# untitled3.net
KiCad netlist of a schematic drawn in EAGLE
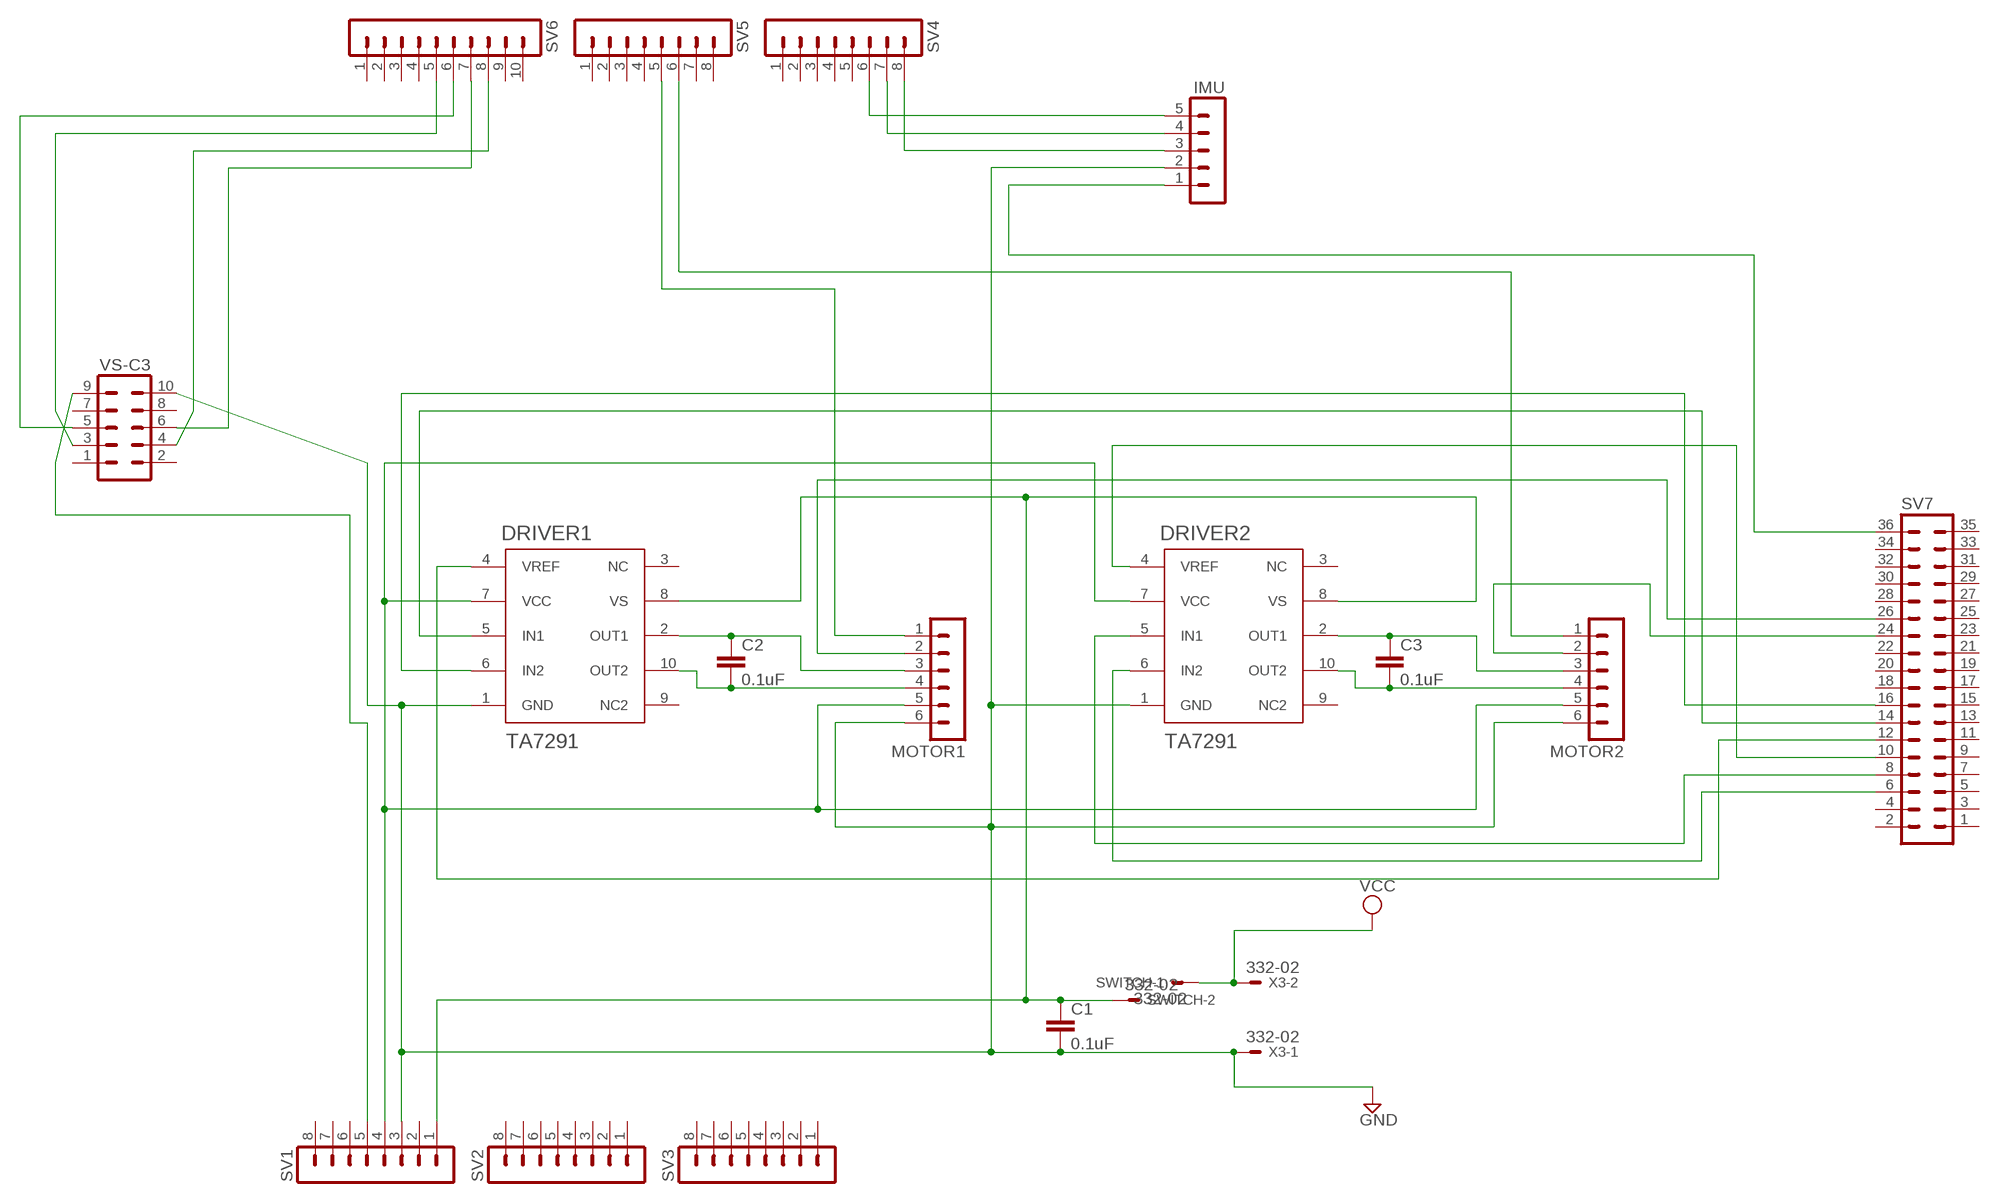
[diagram p0: schematic, sheet 1]

(export (version "E")
  (design (tool "Eeschema 10.0.6"))
  (components
    (comp (ref "C1")
      (value "0.1uF")
      (footprint "eagle-import:C5B2.5")
      (libsource (lib "eagle-import") (part "C5/2.5"))
    )
    (comp (ref "C2")
      (value "0.1uF")
      (footprint "eagle-import:C5B2.5")
      (libsource (lib "eagle-import") (part "C5/2.5"))
    )
    (comp (ref "C3")
      (value "0.1uF")
      (footprint "eagle-import:C5B2.5")
      (libsource (lib "eagle-import") (part "C5/2.5"))
    )
    (comp (ref "DRIVER1")
      (value "TA7291")
      (footprint "eagle-import:HSIP10")
      (libsource (lib "eagle-import") (part "TA7291"))
    )
    (comp (ref "DRIVER2")
      (value "TA7291")
      (footprint "eagle-import:HSIP10")
      (libsource (lib "eagle-import") (part "TA7291"))
    )
    (comp (ref "IMU")
      (value "MA05-1")
      (footprint "eagle-import:MA05-1")
      (libsource (lib "eagle-import") (part "MA05-1"))
    )
    (comp (ref "MOTOR1")
      (value "MA06-1")
      (footprint "eagle-import:MA06-1")
      (libsource (lib "eagle-import") (part "MA06-1"))
    )
    (comp (ref "MOTOR2")
      (value "MA06-1")
      (footprint "eagle-import:MA06-1")
      (libsource (lib "eagle-import") (part "MA06-1"))
    )
    (comp (ref "SV1")
      (value "MA08-1")
      (footprint "eagle-import:MA08-1")
      (libsource (lib "eagle-import") (part "MA08-1"))
    )
    (comp (ref "SV2")
      (value "MA08-1")
      (footprint "eagle-import:MA08-1")
      (libsource (lib "eagle-import") (part "MA08-1"))
    )
    (comp (ref "SV3")
      (value "MA08-1")
      (footprint "eagle-import:MA08-1")
      (libsource (lib "eagle-import") (part "MA08-1"))
    )
    (comp (ref "SV4")
      (value "MA08-1")
      (footprint "eagle-import:MA08-1")
      (libsource (lib "eagle-import") (part "MA08-1"))
    )
    (comp (ref "SV5")
      (value "MA08-1")
      (footprint "eagle-import:MA08-1")
      (libsource (lib "eagle-import") (part "MA08-1"))
    )
    (comp (ref "SV6")
      (value "MA10-1")
      (footprint "eagle-import:MA10-1")
      (libsource (lib "eagle-import") (part "MA10-1"))
    )
    (comp (ref "SV7")
      (value "MA18-2")
      (footprint "eagle-import:MA18-2")
      (libsource (lib "eagle-import") (part "MA18-2"))
    )
    (comp (ref "SWITCH")
      (value "332-02")
      (footprint "eagle-import:332-02")
      (libsource (lib "eagle-import") (part "332-02"))
    )
    (comp (ref "VS-C3")
      (value "MA05-2")
      (footprint "eagle-import:MA05-2")
      (libsource (lib "eagle-import") (part "MA05-2"))
    )
    (comp (ref "X3")
      (value "332-02")
      (footprint "eagle-import:332-02")
      (libsource (lib "eagle-import") (part "332-02"))
    )
  )
  (nets
    (net (code "1") (name "GND") (class "Default")
      (node (ref "C1") (pin "2") (pinfunction "2_2") (pintype "passive"))
      (node (ref "DRIVER1") (pin "1") (pinfunction "GND_1") (pintype "bidirectional"))
      (node (ref "DRIVER2") (pin "1") (pinfunction "GND_1") (pintype "bidirectional"))
      (node (ref "IMU") (pin "2") (pinfunction "2_2") (pintype "passive"))
      (node (ref "MOTOR1") (pin "6") (pinfunction "6_6") (pintype "passive"))
      (node (ref "MOTOR2") (pin "6") (pinfunction "6_6") (pintype "passive"))
      (node (ref "SV1") (pin "3") (pinfunction "3_3") (pintype "passive"))
      (node (ref "VS-C3") (pin "10") (pinfunction "10_10") (pintype "passive"))
      (node (ref "X3") (pin "1") (pinfunction "S_1") (pintype "passive"))
    )
    (net (code "2") (name "Net-(DRIVER1-IN1)") (class "Default")
      (node (ref "DRIVER1") (pin "5") (pinfunction "IN1_5") (pintype "bidirectional"))
      (node (ref "SV7") (pin "14") (pinfunction "14_14") (pintype "passive"))
    )
    (net (code "3") (name "Net-(DRIVER1-IN2)") (class "Default")
      (node (ref "DRIVER1") (pin "6") (pinfunction "IN2_6") (pintype "bidirectional"))
      (node (ref "SV7") (pin "16") (pinfunction "16_16") (pintype "passive"))
    )
    (net (code "4") (name "Net-(DRIVER1-OUT1)") (class "Default")
      (node (ref "C2") (pin "1") (pinfunction "1_1") (pintype "passive"))
      (node (ref "DRIVER1") (pin "2") (pinfunction "OUT1_2") (pintype "bidirectional"))
      (node (ref "MOTOR1") (pin "3") (pinfunction "3_3") (pintype "passive"))
    )
    (net (code "5") (name "Net-(DRIVER1-OUT2)") (class "Default")
      (node (ref "C2") (pin "2") (pinfunction "2_2") (pintype "passive"))
      (node (ref "DRIVER1") (pin "10") (pinfunction "OUT2_10") (pintype "bidirectional"))
      (node (ref "MOTOR1") (pin "4") (pinfunction "4_4") (pintype "passive"))
    )
    (net (code "6") (name "Net-(DRIVER1-VCC)") (class "Default")
      (node (ref "DRIVER1") (pin "7") (pinfunction "VCC_7") (pintype "bidirectional"))
      (node (ref "DRIVER2") (pin "7") (pinfunction "VCC_7") (pintype "bidirectional"))
      (node (ref "MOTOR1") (pin "5") (pinfunction "5_5") (pintype "passive"))
      (node (ref "MOTOR2") (pin "5") (pinfunction "5_5") (pintype "passive"))
      (node (ref "SV1") (pin "4") (pinfunction "4_4") (pintype "passive"))
    )
    (net (code "7") (name "Net-(DRIVER1-VREF)") (class "Default")
      (node (ref "DRIVER1") (pin "4") (pinfunction "VREF_4") (pintype "bidirectional"))
      (node (ref "SV7") (pin "12") (pinfunction "12_12") (pintype "passive"))
    )
    (net (code "8") (name "Net-(DRIVER1-VS)") (class "Default")
      (node (ref "C1") (pin "1") (pinfunction "1_1") (pintype "passive"))
      (node (ref "DRIVER1") (pin "8") (pinfunction "VS_8") (pintype "bidirectional"))
      (node (ref "DRIVER2") (pin "8") (pinfunction "VS_8") (pintype "bidirectional"))
      (node (ref "SV1") (pin "1") (pinfunction "1_1") (pintype "passive"))
      (node (ref "SWITCH") (pin "2") (pinfunction "S_2") (pintype "passive"))
    )
    (net (code "9") (name "Net-(DRIVER2-IN1)") (class "Default")
      (node (ref "DRIVER2") (pin "5") (pinfunction "IN1_5") (pintype "bidirectional"))
      (node (ref "SV7") (pin "8") (pinfunction "8_8") (pintype "passive"))
    )
    (net (code "10") (name "Net-(DRIVER2-IN2)") (class "Default")
      (node (ref "DRIVER2") (pin "6") (pinfunction "IN2_6") (pintype "bidirectional"))
      (node (ref "SV7") (pin "6") (pinfunction "6_6") (pintype "passive"))
    )
    (net (code "11") (name "Net-(DRIVER2-OUT1)") (class "Default")
      (node (ref "C3") (pin "1") (pinfunction "1_1") (pintype "passive"))
      (node (ref "DRIVER2") (pin "2") (pinfunction "OUT1_2") (pintype "bidirectional"))
      (node (ref "MOTOR2") (pin "3") (pinfunction "3_3") (pintype "passive"))
    )
    (net (code "12") (name "Net-(DRIVER2-OUT2)") (class "Default")
      (node (ref "C3") (pin "2") (pinfunction "2_2") (pintype "passive"))
      (node (ref "DRIVER2") (pin "10") (pinfunction "OUT2_10") (pintype "bidirectional"))
      (node (ref "MOTOR2") (pin "4") (pinfunction "4_4") (pintype "passive"))
    )
    (net (code "13") (name "Net-(DRIVER2-VREF)") (class "Default")
      (node (ref "DRIVER2") (pin "4") (pinfunction "VREF_4") (pintype "bidirectional"))
      (node (ref "SV7") (pin "10") (pinfunction "10_10") (pintype "passive"))
    )
    (net (code "14") (name "Net-(IMU-Pad1)") (class "Default")
      (node (ref "IMU") (pin "1") (pinfunction "1_1") (pintype "passive"))
      (node (ref "SV7") (pin "36") (pinfunction "36_36") (pintype "passive"))
    )
    (net (code "15") (name "Net-(IMU-Pad3)") (class "Default")
      (node (ref "IMU") (pin "3") (pinfunction "3_3") (pintype "passive"))
      (node (ref "SV4") (pin "8") (pinfunction "8_8") (pintype "passive"))
    )
    (net (code "16") (name "Net-(IMU-Pad4)") (class "Default")
      (node (ref "IMU") (pin "4") (pinfunction "4_4") (pintype "passive"))
      (node (ref "SV4") (pin "7") (pinfunction "7_7") (pintype "passive"))
    )
    (net (code "17") (name "Net-(IMU-Pad5)") (class "Default")
      (node (ref "IMU") (pin "5") (pinfunction "5_5") (pintype "passive"))
      (node (ref "SV4") (pin "6") (pinfunction "6_6") (pintype "passive"))
    )
    (net (code "18") (name "Net-(MOTOR1-Pad1)") (class "Default")
      (node (ref "MOTOR1") (pin "1") (pinfunction "1_1") (pintype "passive"))
      (node (ref "SV5") (pin "5") (pinfunction "5_5") (pintype "passive"))
    )
    (net (code "19") (name "Net-(MOTOR1-Pad2)") (class "Default")
      (node (ref "MOTOR1") (pin "2") (pinfunction "2_2") (pintype "passive"))
      (node (ref "SV7") (pin "26") (pinfunction "26_26") (pintype "passive"))
    )
    (net (code "20") (name "Net-(MOTOR2-Pad1)") (class "Default")
      (node (ref "MOTOR2") (pin "1") (pinfunction "1_1") (pintype "passive"))
      (node (ref "SV5") (pin "6") (pinfunction "6_6") (pintype "passive"))
    )
    (net (code "21") (name "Net-(MOTOR2-Pad2)") (class "Default")
      (node (ref "MOTOR2") (pin "2") (pinfunction "2_2") (pintype "passive"))
      (node (ref "SV7") (pin "24") (pinfunction "24_24") (pintype "passive"))
    )
    (net (code "22") (name "Net-(SV1-Pad5)") (class "Default")
      (node (ref "SV1") (pin "5") (pinfunction "5_5") (pintype "passive"))
      (node (ref "VS-C3") (pin "9") (pinfunction "9_9") (pintype "passive"))
    )
    (net (code "23") (name "Net-(SV6-Pad5)") (class "Default")
      (node (ref "SV6") (pin "5") (pinfunction "5_5") (pintype "passive"))
      (node (ref "VS-C3") (pin "3") (pinfunction "3_3") (pintype "passive"))
    )
    (net (code "24") (name "Net-(SV6-Pad6)") (class "Default")
      (node (ref "SV6") (pin "6") (pinfunction "6_6") (pintype "passive"))
      (node (ref "VS-C3") (pin "5") (pinfunction "5_5") (pintype "passive"))
    )
    (net (code "25") (name "Net-(SV6-Pad7)") (class "Default")
      (node (ref "SV6") (pin "7") (pinfunction "7_7") (pintype "passive"))
      (node (ref "VS-C3") (pin "6") (pinfunction "6_6") (pintype "passive"))
    )
    (net (code "26") (name "Net-(SV6-Pad8)") (class "Default")
      (node (ref "SV6") (pin "8") (pinfunction "8_8") (pintype "passive"))
      (node (ref "VS-C3") (pin "4") (pinfunction "4_4") (pintype "passive"))
    )
    (net (code "27") (name "VCC") (class "Default")
      (node (ref "SWITCH") (pin "1") (pinfunction "S_1") (pintype "passive"))
      (node (ref "X3") (pin "2") (pinfunction "S_2") (pintype "passive"))
    )
    (net (code "28") (name "unconnected-(DRIVER1-NC-Pad3)") (class "Default")
      (node (ref "DRIVER1") (pin "3") (pinfunction "NC_3") (pintype "bidirectional"))
    )
    (net (code "29") (name "unconnected-(DRIVER1-NC2-Pad9)") (class "Default")
      (node (ref "DRIVER1") (pin "9") (pinfunction "NC2_9") (pintype "bidirectional"))
    )
    (net (code "30") (name "unconnected-(DRIVER2-NC-Pad3)") (class "Default")
      (node (ref "DRIVER2") (pin "3") (pinfunction "NC_3") (pintype "bidirectional"))
    )
    (net (code "31") (name "unconnected-(DRIVER2-NC2-Pad9)") (class "Default")
      (node (ref "DRIVER2") (pin "9") (pinfunction "NC2_9") (pintype "bidirectional"))
    )
    (net (code "32") (name "unconnected-(SV1-Pad2)") (class "Default")
      (node (ref "SV1") (pin "2") (pinfunction "2_2") (pintype "passive"))
    )
    (net (code "33") (name "unconnected-(SV1-Pad6)") (class "Default")
      (node (ref "SV1") (pin "6") (pinfunction "6_6") (pintype "passive"))
    )
    (net (code "34") (name "unconnected-(SV1-Pad7)") (class "Default")
      (node (ref "SV1") (pin "7") (pinfunction "7_7") (pintype "passive"))
    )
    (net (code "35") (name "unconnected-(SV1-Pad8)") (class "Default")
      (node (ref "SV1") (pin "8") (pinfunction "8_8") (pintype "passive"))
    )
    (net (code "36") (name "unconnected-(SV2-Pad1)") (class "Default")
      (node (ref "SV2") (pin "1") (pinfunction "1_1") (pintype "passive"))
    )
    (net (code "37") (name "unconnected-(SV2-Pad2)") (class "Default")
      (node (ref "SV2") (pin "2") (pinfunction "2_2") (pintype "passive"))
    )
    (net (code "38") (name "unconnected-(SV2-Pad3)") (class "Default")
      (node (ref "SV2") (pin "3") (pinfunction "3_3") (pintype "passive"))
    )
    (net (code "39") (name "unconnected-(SV2-Pad4)") (class "Default")
      (node (ref "SV2") (pin "4") (pinfunction "4_4") (pintype "passive"))
    )
    (net (code "40") (name "unconnected-(SV2-Pad5)") (class "Default")
      (node (ref "SV2") (pin "5") (pinfunction "5_5") (pintype "passive"))
    )
    (net (code "41") (name "unconnected-(SV2-Pad6)") (class "Default")
      (node (ref "SV2") (pin "6") (pinfunction "6_6") (pintype "passive"))
    )
    (net (code "42") (name "unconnected-(SV2-Pad7)") (class "Default")
      (node (ref "SV2") (pin "7") (pinfunction "7_7") (pintype "passive"))
    )
    (net (code "43") (name "unconnected-(SV2-Pad8)") (class "Default")
      (node (ref "SV2") (pin "8") (pinfunction "8_8") (pintype "passive"))
    )
    (net (code "44") (name "unconnected-(SV3-Pad1)") (class "Default")
      (node (ref "SV3") (pin "1") (pinfunction "1_1") (pintype "passive"))
    )
    (net (code "45") (name "unconnected-(SV3-Pad2)") (class "Default")
      (node (ref "SV3") (pin "2") (pinfunction "2_2") (pintype "passive"))
    )
    (net (code "46") (name "unconnected-(SV3-Pad3)") (class "Default")
      (node (ref "SV3") (pin "3") (pinfunction "3_3") (pintype "passive"))
    )
    (net (code "47") (name "unconnected-(SV3-Pad4)") (class "Default")
      (node (ref "SV3") (pin "4") (pinfunction "4_4") (pintype "passive"))
    )
    (net (code "48") (name "unconnected-(SV3-Pad5)") (class "Default")
      (node (ref "SV3") (pin "5") (pinfunction "5_5") (pintype "passive"))
    )
    (net (code "49") (name "unconnected-(SV3-Pad6)") (class "Default")
      (node (ref "SV3") (pin "6") (pinfunction "6_6") (pintype "passive"))
    )
    (net (code "50") (name "unconnected-(SV3-Pad7)") (class "Default")
      (node (ref "SV3") (pin "7") (pinfunction "7_7") (pintype "passive"))
    )
    (net (code "51") (name "unconnected-(SV3-Pad8)") (class "Default")
      (node (ref "SV3") (pin "8") (pinfunction "8_8") (pintype "passive"))
    )
    (net (code "52") (name "unconnected-(SV4-Pad1)") (class "Default")
      (node (ref "SV4") (pin "1") (pinfunction "1_1") (pintype "passive"))
    )
    (net (code "53") (name "unconnected-(SV4-Pad2)") (class "Default")
      (node (ref "SV4") (pin "2") (pinfunction "2_2") (pintype "passive"))
    )
    (net (code "54") (name "unconnected-(SV4-Pad3)") (class "Default")
      (node (ref "SV4") (pin "3") (pinfunction "3_3") (pintype "passive"))
    )
    (net (code "55") (name "unconnected-(SV4-Pad4)") (class "Default")
      (node (ref "SV4") (pin "4") (pinfunction "4_4") (pintype "passive"))
    )
    (net (code "56") (name "unconnected-(SV4-Pad5)") (class "Default")
      (node (ref "SV4") (pin "5") (pinfunction "5_5") (pintype "passive"))
    )
    (net (code "57") (name "unconnected-(SV5-Pad1)") (class "Default")
      (node (ref "SV5") (pin "1") (pinfunction "1_1") (pintype "passive"))
    )
    (net (code "58") (name "unconnected-(SV5-Pad2)") (class "Default")
      (node (ref "SV5") (pin "2") (pinfunction "2_2") (pintype "passive"))
    )
    (net (code "59") (name "unconnected-(SV5-Pad3)") (class "Default")
      (node (ref "SV5") (pin "3") (pinfunction "3_3") (pintype "passive"))
    )
    (net (code "60") (name "unconnected-(SV5-Pad4)") (class "Default")
      (node (ref "SV5") (pin "4") (pinfunction "4_4") (pintype "passive"))
    )
    (net (code "61") (name "unconnected-(SV5-Pad7)") (class "Default")
      (node (ref "SV5") (pin "7") (pinfunction "7_7") (pintype "passive"))
    )
    (net (code "62") (name "unconnected-(SV5-Pad8)") (class "Default")
      (node (ref "SV5") (pin "8") (pinfunction "8_8") (pintype "passive"))
    )
    (net (code "63") (name "unconnected-(SV6-Pad1)") (class "Default")
      (node (ref "SV6") (pin "1") (pinfunction "1_1") (pintype "passive"))
    )
    (net (code "64") (name "unconnected-(SV6-Pad2)") (class "Default")
      (node (ref "SV6") (pin "2") (pinfunction "2_2") (pintype "passive"))
    )
    (net (code "65") (name "unconnected-(SV6-Pad3)") (class "Default")
      (node (ref "SV6") (pin "3") (pinfunction "3_3") (pintype "passive"))
    )
    (net (code "66") (name "unconnected-(SV6-Pad4)") (class "Default")
      (node (ref "SV6") (pin "4") (pinfunction "4_4") (pintype "passive"))
    )
    (net (code "67") (name "unconnected-(SV6-Pad9)") (class "Default")
      (node (ref "SV6") (pin "9") (pinfunction "9_9") (pintype "passive"))
    )
    (net (code "68") (name "unconnected-(SV6-Pad10)") (class "Default")
      (node (ref "SV6") (pin "10") (pinfunction "10_10") (pintype "passive"))
    )
    (net (code "69") (name "unconnected-(SV7-Pad1)") (class "Default")
      (node (ref "SV7") (pin "1") (pinfunction "1_1") (pintype "passive"))
    )
    (net (code "70") (name "unconnected-(SV7-Pad2)") (class "Default")
      (node (ref "SV7") (pin "2") (pinfunction "2_2") (pintype "passive"))
    )
    (net (code "71") (name "unconnected-(SV7-Pad3)") (class "Default")
      (node (ref "SV7") (pin "3") (pinfunction "3_3") (pintype "passive"))
    )
    (net (code "72") (name "unconnected-(SV7-Pad4)") (class "Default")
      (node (ref "SV7") (pin "4") (pinfunction "4_4") (pintype "passive"))
    )
    (net (code "73") (name "unconnected-(SV7-Pad5)") (class "Default")
      (node (ref "SV7") (pin "5") (pinfunction "5_5") (pintype "passive"))
    )
    (net (code "74") (name "unconnected-(SV7-Pad7)") (class "Default")
      (node (ref "SV7") (pin "7") (pinfunction "7_7") (pintype "passive"))
    )
    (net (code "75") (name "unconnected-(SV7-Pad9)") (class "Default")
      (node (ref "SV7") (pin "9") (pinfunction "9_9") (pintype "passive"))
    )
    (net (code "76") (name "unconnected-(SV7-Pad11)") (class "Default")
      (node (ref "SV7") (pin "11") (pinfunction "11_11") (pintype "passive"))
    )
    (net (code "77") (name "unconnected-(SV7-Pad13)") (class "Default")
      (node (ref "SV7") (pin "13") (pinfunction "13_13") (pintype "passive"))
    )
    (net (code "78") (name "unconnected-(SV7-Pad15)") (class "Default")
      (node (ref "SV7") (pin "15") (pinfunction "15_15") (pintype "passive"))
    )
    (net (code "79") (name "unconnected-(SV7-Pad17)") (class "Default")
      (node (ref "SV7") (pin "17") (pinfunction "17_17") (pintype "passive"))
    )
    (net (code "80") (name "unconnected-(SV7-Pad18)") (class "Default")
      (node (ref "SV7") (pin "18") (pinfunction "18_18") (pintype "passive"))
    )
    (net (code "81") (name "unconnected-(SV7-Pad19)") (class "Default")
      (node (ref "SV7") (pin "19") (pinfunction "19_19") (pintype "passive"))
    )
    (net (code "82") (name "unconnected-(SV7-Pad20)") (class "Default")
      (node (ref "SV7") (pin "20") (pinfunction "20_20") (pintype "passive"))
    )
    (net (code "83") (name "unconnected-(SV7-Pad21)") (class "Default")
      (node (ref "SV7") (pin "21") (pinfunction "21_21") (pintype "passive"))
    )
    (net (code "84") (name "unconnected-(SV7-Pad22)") (class "Default")
      (node (ref "SV7") (pin "22") (pinfunction "22_22") (pintype "passive"))
    )
    (net (code "85") (name "unconnected-(SV7-Pad23)") (class "Default")
      (node (ref "SV7") (pin "23") (pinfunction "23_23") (pintype "passive"))
    )
    (net (code "86") (name "unconnected-(SV7-Pad25)") (class "Default")
      (node (ref "SV7") (pin "25") (pinfunction "25_25") (pintype "passive"))
    )
    (net (code "87") (name "unconnected-(SV7-Pad27)") (class "Default")
      (node (ref "SV7") (pin "27") (pinfunction "27_27") (pintype "passive"))
    )
    (net (code "88") (name "unconnected-(SV7-Pad28)") (class "Default")
      (node (ref "SV7") (pin "28") (pinfunction "28_28") (pintype "passive"))
    )
    (net (code "89") (name "unconnected-(SV7-Pad29)") (class "Default")
      (node (ref "SV7") (pin "29") (pinfunction "29_29") (pintype "passive"))
    )
    (net (code "90") (name "unconnected-(SV7-Pad30)") (class "Default")
      (node (ref "SV7") (pin "30") (pinfunction "30_30") (pintype "passive"))
    )
    (net (code "91") (name "unconnected-(SV7-Pad31)") (class "Default")
      (node (ref "SV7") (pin "31") (pinfunction "31_31") (pintype "passive"))
    )
    (net (code "92") (name "unconnected-(SV7-Pad32)") (class "Default")
      (node (ref "SV7") (pin "32") (pinfunction "32_32") (pintype "passive"))
    )
    (net (code "93") (name "unconnected-(SV7-Pad33)") (class "Default")
      (node (ref "SV7") (pin "33") (pinfunction "33_33") (pintype "passive"))
    )
    (net (code "94") (name "unconnected-(SV7-Pad34)") (class "Default")
      (node (ref "SV7") (pin "34") (pinfunction "34_34") (pintype "passive"))
    )
    (net (code "95") (name "unconnected-(SV7-Pad35)") (class "Default")
      (node (ref "SV7") (pin "35") (pinfunction "35_35") (pintype "passive"))
    )
    (net (code "96") (name "unconnected-(VS-C3-Pad1)") (class "Default")
      (node (ref "VS-C3") (pin "1") (pinfunction "1_1") (pintype "passive"))
    )
    (net (code "97") (name "unconnected-(VS-C3-Pad2)") (class "Default")
      (node (ref "VS-C3") (pin "2") (pinfunction "2_2") (pintype "passive"))
    )
    (net (code "98") (name "unconnected-(VS-C3-Pad7)") (class "Default")
      (node (ref "VS-C3") (pin "7") (pinfunction "7_7") (pintype "passive"))
    )
    (net (code "99") (name "unconnected-(VS-C3-Pad8)") (class "Default")
      (node (ref "VS-C3") (pin "8") (pinfunction "8_8") (pintype "passive"))
    )
  )
)
